# Dilbert-Badge.net
KiCad netlist of a schematic drawn in EAGLE
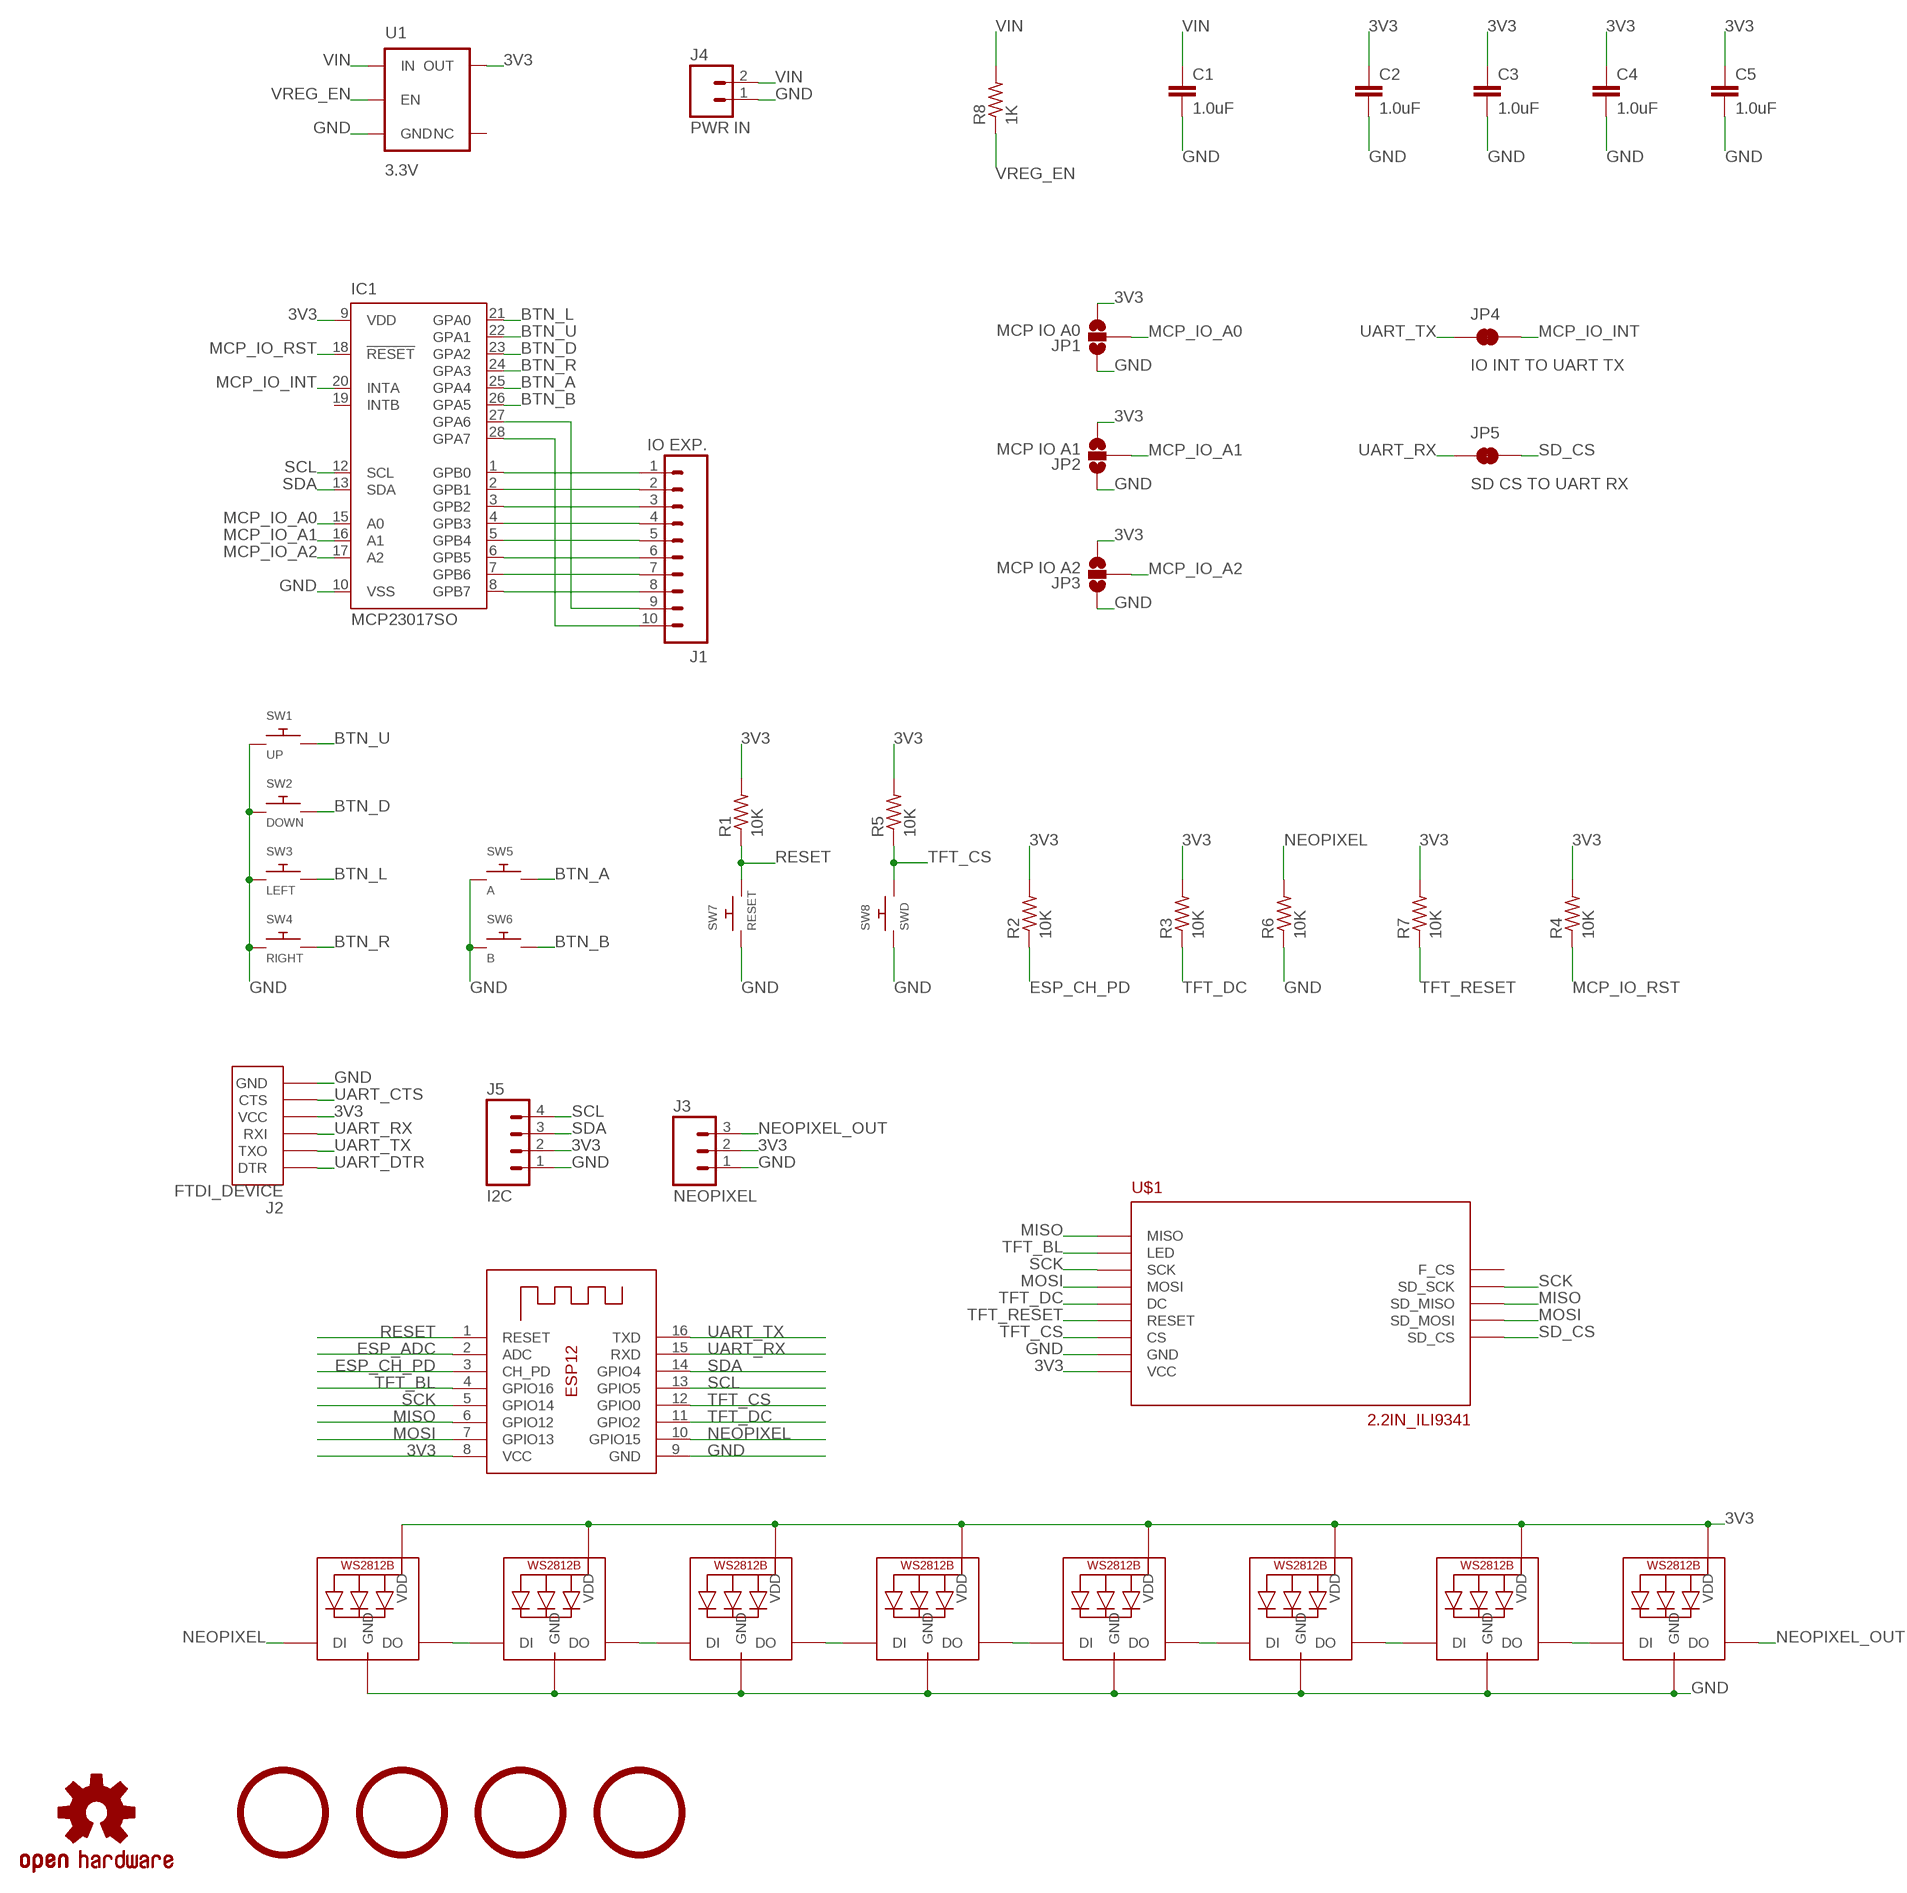
[diagram p0: schematic, sheet 1]

(export (version "E")
  (design (tool "Eeschema 10.0.6"))
  (components
    (comp (ref "C1")
      (value "1.0uF")
      (footprint "eagle-import:0805-CAP")
      (libsource (lib "eagle-import") (part "1.0UF-25V-+80/-20(0805){dblquote}"))
    )
    (comp (ref "C2")
      (value "1.0uF")
      (footprint "eagle-import:0805-CAP")
      (libsource (lib "eagle-import") (part "1.0UF-25V-+80/-20(0805){dblquote}"))
    )
    (comp (ref "C3")
      (value "1.0uF")
      (footprint "eagle-import:0805-CAP")
      (libsource (lib "eagle-import") (part "1.0UF-25V-+80/-20(0805){dblquote}"))
    )
    (comp (ref "C4")
      (value "1.0uF")
      (footprint "eagle-import:0805-CAP")
      (libsource (lib "eagle-import") (part "1.0UF-25V-+80/-20(0805){dblquote}"))
    )
    (comp (ref "C5")
      (value "1.0uF")
      (footprint "eagle-import:0805-CAP")
      (libsource (lib "eagle-import") (part "1.0UF-25V-+80/-20(0805){dblquote}"))
    )
    (comp (ref "IC1")
      (value "MCP23017SO")
      (footprint "eagle-import:SO28W")
      (libsource (lib "eagle-import") (part "MCP23017SO"))
    )
    (comp (ref "J1")
      (value "IO EXP.")
      (footprint "eagle-import:1X10")
      (libsource (lib "eagle-import") (part "M10SILK_FEMALE_PTH"))
    )
    (comp (ref "J2")
      (value "FTDI_DEVICE")
      (footprint "eagle-import:FTDI_DEVICE_SIDE")
      (libsource (lib "eagle-import") (part "FTDI_DEVICE"))
    )
    (comp (ref "J3")
      (value "NEOPIXEL")
      (footprint "eagle-import:1X03")
      (libsource (lib "eagle-import") (part "M03PTH"))
    )
    (comp (ref "J4")
      (value "PWR IN")
      (footprint "eagle-import:1X02")
      (libsource (lib "eagle-import") (part "M02PTH"))
    )
    (comp (ref "J5")
      (value "I2C")
      (footprint "eagle-import:1X04")
      (libsource (lib "eagle-import") (part "M04PTH"))
    )
    (comp (ref "JP1")
      (value "MCP IO A0")
      (footprint "eagle-import:PAD-JUMPER-3-NO_YES_SILK")
      (libsource (lib "eagle-import") (part "JUMPER-PAD-3-NOYES_SILK"))
    )
    (comp (ref "JP2")
      (value "MCP IO A1")
      (footprint "eagle-import:PAD-JUMPER-3-NO_YES_SILK")
      (libsource (lib "eagle-import") (part "JUMPER-PAD-3-NOYES_SILK"))
    )
    (comp (ref "JP3")
      (value "MCP IO A2")
      (footprint "eagle-import:PAD-JUMPER-3-NO_YES_SILK")
      (libsource (lib "eagle-import") (part "JUMPER-PAD-3-NOYES_SILK"))
    )
    (comp (ref "JP4")
      (value "IO INT TO UART TX")
      (footprint "eagle-import:PAD-JUMPER-2-NC_BY_TRACE_NO_SILK")
      (libsource (lib "eagle-import") (part "JUMPER-PAD-2-NC_BY_TRACENO_SILK"))
    )
    (comp (ref "JP5")
      (value "SD CS TO UART RX")
      (footprint "eagle-import:PAD-JUMPER-2-NC_BY_TRACE_NO_SILK")
      (libsource (lib "eagle-import") (part "JUMPER-PAD-2-NC_BY_TRACENO_SILK"))
    )
    (comp (ref "LED1")
      (value "WS2812B5050")
      (footprint "eagle-import:WS2812B")
      (libsource (lib "eagle-import") (part "WS2812B5050"))
    )
    (comp (ref "LED2")
      (value "WS2812B5050")
      (footprint "eagle-import:WS2812B")
      (libsource (lib "eagle-import") (part "WS2812B5050"))
    )
    (comp (ref "LED3")
      (value "WS2812B5050")
      (footprint "eagle-import:WS2812B")
      (libsource (lib "eagle-import") (part "WS2812B5050"))
    )
    (comp (ref "LED4")
      (value "WS2812B5050")
      (footprint "eagle-import:WS2812B")
      (libsource (lib "eagle-import") (part "WS2812B5050"))
    )
    (comp (ref "LED5")
      (value "WS2812B5050")
      (footprint "eagle-import:WS2812B")
      (libsource (lib "eagle-import") (part "WS2812B5050"))
    )
    (comp (ref "LED6")
      (value "WS2812B5050")
      (footprint "eagle-import:WS2812B")
      (libsource (lib "eagle-import") (part "WS2812B5050"))
    )
    (comp (ref "LED7")
      (value "WS2812B5050")
      (footprint "eagle-import:WS2812B")
      (libsource (lib "eagle-import") (part "WS2812B5050"))
    )
    (comp (ref "LED8")
      (value "WS2812B5050")
      (footprint "eagle-import:WS2812B")
      (libsource (lib "eagle-import") (part "WS2812B5050"))
    )
    (comp (ref "LOGO1")
      (value "OSHW-LOGOL")
      (footprint "eagle-import:OSHW-LOGO-L")
      (libsource (lib "eagle-import") (part "OSHW-LOGOL"))
    )
    (comp (ref "R1")
      (value "10K")
      (footprint "eagle-import:R0805")
      (libsource (lib "eagle-import") (part "R-US_R0805"))
    )
    (comp (ref "R2")
      (value "10K")
      (footprint "eagle-import:R0805")
      (libsource (lib "eagle-import") (part "R-US_R0805"))
    )
    (comp (ref "R3")
      (value "10K")
      (footprint "eagle-import:R0805")
      (libsource (lib "eagle-import") (part "R-US_R0805"))
    )
    (comp (ref "R4")
      (value "10K")
      (footprint "eagle-import:R0805")
      (libsource (lib "eagle-import") (part "R-US_R0805"))
    )
    (comp (ref "R5")
      (value "10K")
      (footprint "eagle-import:R0805")
      (libsource (lib "eagle-import") (part "R-US_R0805"))
    )
    (comp (ref "R6")
      (value "10K")
      (footprint "eagle-import:R0805")
      (libsource (lib "eagle-import") (part "R-US_R0805"))
    )
    (comp (ref "R7")
      (value "10K")
      (footprint "eagle-import:R0805")
      (libsource (lib "eagle-import") (part "R-US_R0805"))
    )
    (comp (ref "R8")
      (value "1K")
      (footprint "eagle-import:R0805")
      (libsource (lib "eagle-import") (part "R-US_R0805"))
    )
    (comp (ref "SW1")
      (value "UP")
      (footprint "eagle-import:TACT_PANA-EVQ")
      (libsource (lib "eagle-import") (part "SWITCH_PUSHBUTTONEVQ-PE"))
    )
    (comp (ref "SW2")
      (value "DOWN")
      (footprint "eagle-import:TACT_PANA-EVQ")
      (libsource (lib "eagle-import") (part "SWITCH_PUSHBUTTONEVQ-PE"))
    )
    (comp (ref "SW3")
      (value "LEFT")
      (footprint "eagle-import:TACT_PANA-EVQ")
      (libsource (lib "eagle-import") (part "SWITCH_PUSHBUTTONEVQ-PE"))
    )
    (comp (ref "SW4")
      (value "RIGHT")
      (footprint "eagle-import:TACT_PANA-EVQ")
      (libsource (lib "eagle-import") (part "SWITCH_PUSHBUTTONEVQ-PE"))
    )
    (comp (ref "SW5")
      (value "A")
      (footprint "eagle-import:TACT_PANA-EVQ")
      (libsource (lib "eagle-import") (part "SWITCH_PUSHBUTTONEVQ-PE"))
    )
    (comp (ref "SW6")
      (value "B")
      (footprint "eagle-import:TACT_PANA-EVQ")
      (libsource (lib "eagle-import") (part "SWITCH_PUSHBUTTONEVQ-PE"))
    )
    (comp (ref "SW7")
      (value "RESET")
      (footprint "eagle-import:TACT_PANA-EVQ")
      (libsource (lib "eagle-import") (part "SWITCH_PUSHBUTTONEVQ-PE"))
    )
    (comp (ref "SW8")
      (value "SWD")
      (footprint "eagle-import:TACT_PANA-EVQ")
      (libsource (lib "eagle-import") (part "SWITCH_PUSHBUTTONEVQ-PE"))
    )
    (comp (ref "U$1")
      (value "2.2IN_ILI9341")
      (footprint "eagle-import:2.2IN_ILI9341")
      (libsource (lib "eagle-import") (part "2.2IN_ILI9341"))
    )
    (comp (ref "U$2")
      (value "5MM_MOUNTING_HOLE")
      (footprint "eagle-import:5MM_HOLE")
      (libsource (lib "eagle-import") (part "5MM_MOUNTING_HOLE"))
    )
    (comp (ref "U$3")
      (value "5MM_MOUNTING_HOLE")
      (footprint "eagle-import:5MM_HOLE")
      (libsource (lib "eagle-import") (part "5MM_MOUNTING_HOLE"))
    )
    (comp (ref "U$4")
      (value "5MM_MOUNTING_HOLE")
      (footprint "eagle-import:5MM_HOLE")
      (libsource (lib "eagle-import") (part "5MM_MOUNTING_HOLE"))
    )
    (comp (ref "U$5")
      (value "5MM_MOUNTING_HOLE")
      (footprint "eagle-import:5MM_HOLE")
      (libsource (lib "eagle-import") (part "5MM_MOUNTING_HOLE"))
    )
    (comp (ref "U1")
      (value "3.3V")
      (footprint "eagle-import:SOT23-5")
      (libsource (lib "eagle-import") (part "V_REG_AP2112K-3.3V"))
    )
    (comp (ref "X1")
      (value "ESP-12")
      (footprint "eagle-import:ESP-12")
      (libsource (lib "eagle-import") (part "ESP-12"))
    )
  )
  (nets
    (net (code "1") (name "/3V3") (class "Default")
      (node (ref "C2") (pin "1") (pinfunction "1_1") (pintype "passive"))
      (node (ref "C3") (pin "1") (pinfunction "1_1") (pintype "passive"))
      (node (ref "C4") (pin "1") (pinfunction "1_1") (pintype "passive"))
      (node (ref "C5") (pin "1") (pinfunction "1_1") (pintype "passive"))
      (node (ref "IC1") (pin "9") (pinfunction "VDD_9") (pintype "power_in"))
      (node (ref "J2") (pin "P$4") (pinfunction "VCC_P$4") (pintype "bidirectional"))
      (node (ref "J3") (pin "2") (pinfunction "2_2") (pintype "passive"))
      (node (ref "J5") (pin "2") (pinfunction "2_2") (pintype "passive"))
      (node (ref "JP1") (pin "3") (pinfunction "3_3") (pintype "passive"))
      (node (ref "JP2") (pin "3") (pinfunction "3_3") (pintype "passive"))
      (node (ref "JP3") (pin "3") (pinfunction "3_3") (pintype "passive"))
      (node (ref "LED1") (pin "1-VDD") (pinfunction "VDD_1-VDD") (pintype "power_in"))
      (node (ref "LED2") (pin "1-VDD") (pinfunction "VDD_1-VDD") (pintype "power_in"))
      (node (ref "LED3") (pin "1-VDD") (pinfunction "VDD_1-VDD") (pintype "power_in"))
      (node (ref "LED4") (pin "1-VDD") (pinfunction "VDD_1-VDD") (pintype "power_in"))
      (node (ref "LED5") (pin "1-VDD") (pinfunction "VDD_1-VDD") (pintype "power_in"))
      (node (ref "LED6") (pin "1-VDD") (pinfunction "VDD_1-VDD") (pintype "power_in"))
      (node (ref "LED7") (pin "1-VDD") (pinfunction "VDD_1-VDD") (pintype "power_in"))
      (node (ref "LED8") (pin "1-VDD") (pinfunction "VDD_1-VDD") (pintype "power_in"))
      (node (ref "R1") (pin "2") (pinfunction "2_2") (pintype "passive"))
      (node (ref "R2") (pin "2") (pinfunction "2_2") (pintype "passive"))
      (node (ref "R3") (pin "2") (pinfunction "2_2") (pintype "passive"))
      (node (ref "R4") (pin "2") (pinfunction "2_2") (pintype "passive"))
      (node (ref "R5") (pin "2") (pinfunction "2_2") (pintype "passive"))
      (node (ref "R7") (pin "2") (pinfunction "2_2") (pintype "passive"))
      (node (ref "U$1") (pin "VCC") (pinfunction "VCC_VCC") (pintype "power_in"))
      (node (ref "U1") (pin "5") (pinfunction "OUT_5") (pintype "passive"))
      (node (ref "X1") (pin "8") (pinfunction "VCC_8") (pintype "power_in"))
    )
    (net (code "2") (name "/BTN_A") (class "Default")
      (node (ref "IC1") (pin "25") (pinfunction "GPA4_25") (pintype "bidirectional"))
      (node (ref "SW5") (pin "P$2") (pinfunction "P$2_P$2") (pintype "passive"))
    )
    (net (code "3") (name "/BTN_B") (class "Default")
      (node (ref "IC1") (pin "26") (pinfunction "GPA5_26") (pintype "bidirectional"))
      (node (ref "SW6") (pin "P$2") (pinfunction "P$2_P$2") (pintype "passive"))
    )
    (net (code "4") (name "/BTN_D") (class "Default")
      (node (ref "IC1") (pin "23") (pinfunction "GPA2_23") (pintype "bidirectional"))
      (node (ref "SW2") (pin "P$2") (pinfunction "P$2_P$2") (pintype "passive"))
    )
    (net (code "5") (name "/BTN_L") (class "Default")
      (node (ref "IC1") (pin "21") (pinfunction "GPA0_21") (pintype "bidirectional"))
      (node (ref "SW3") (pin "P$2") (pinfunction "P$2_P$2") (pintype "passive"))
    )
    (net (code "6") (name "/BTN_R") (class "Default")
      (node (ref "IC1") (pin "24") (pinfunction "GPA3_24") (pintype "bidirectional"))
      (node (ref "SW4") (pin "P$2") (pinfunction "P$2_P$2") (pintype "passive"))
    )
    (net (code "7") (name "/BTN_U") (class "Default")
      (node (ref "IC1") (pin "22") (pinfunction "GPA1_22") (pintype "bidirectional"))
      (node (ref "SW1") (pin "P$2") (pinfunction "P$2_P$2") (pintype "passive"))
    )
    (net (code "8") (name "/ESP_ADC") (class "Default")
      (node (ref "X1") (pin "2") (pinfunction "ADC_2") (pintype "passive"))
    )
    (net (code "9") (name "/ESP_CH_PD") (class "Default")
      (node (ref "R2") (pin "1") (pinfunction "1_1") (pintype "passive"))
      (node (ref "X1") (pin "3") (pinfunction "CH_PD_3") (pintype "input"))
    )
    (net (code "10") (name "/GND") (class "Default")
      (node (ref "C1") (pin "2") (pinfunction "2_2") (pintype "passive"))
      (node (ref "C2") (pin "2") (pinfunction "2_2") (pintype "passive"))
      (node (ref "C3") (pin "2") (pinfunction "2_2") (pintype "passive"))
      (node (ref "C4") (pin "2") (pinfunction "2_2") (pintype "passive"))
      (node (ref "C5") (pin "2") (pinfunction "2_2") (pintype "passive"))
      (node (ref "IC1") (pin "10") (pinfunction "VSS_10") (pintype "power_in"))
      (node (ref "J2") (pin "P$6") (pinfunction "GND_P$6") (pintype "bidirectional"))
      (node (ref "J3") (pin "1") (pinfunction "1_1") (pintype "passive"))
      (node (ref "J4") (pin "1") (pinfunction "1_1") (pintype "passive"))
      (node (ref "J5") (pin "1") (pinfunction "1_1") (pintype "passive"))
      (node (ref "JP1") (pin "1") (pinfunction "1_1") (pintype "passive"))
      (node (ref "JP2") (pin "1") (pinfunction "1_1") (pintype "passive"))
      (node (ref "JP3") (pin "1") (pinfunction "1_1") (pintype "passive"))
      (node (ref "LED1") (pin "3-GND") (pinfunction "GND_3-GND") (pintype "power_in"))
      (node (ref "LED2") (pin "3-GND") (pinfunction "GND_3-GND") (pintype "power_in"))
      (node (ref "LED3") (pin "3-GND") (pinfunction "GND_3-GND") (pintype "power_in"))
      (node (ref "LED4") (pin "3-GND") (pinfunction "GND_3-GND") (pintype "power_in"))
      (node (ref "LED5") (pin "3-GND") (pinfunction "GND_3-GND") (pintype "power_in"))
      (node (ref "LED6") (pin "3-GND") (pinfunction "GND_3-GND") (pintype "power_in"))
      (node (ref "LED7") (pin "3-GND") (pinfunction "GND_3-GND") (pintype "power_in"))
      (node (ref "LED8") (pin "3-GND") (pinfunction "GND_3-GND") (pintype "power_in"))
      (node (ref "R6") (pin "1") (pinfunction "1_1") (pintype "passive"))
      (node (ref "SW1") (pin "P$1") (pinfunction "P$1_P$1") (pintype "passive"))
      (node (ref "SW2") (pin "P$1") (pinfunction "P$1_P$1") (pintype "passive"))
      (node (ref "SW3") (pin "P$1") (pinfunction "P$1_P$1") (pintype "passive"))
      (node (ref "SW4") (pin "P$1") (pinfunction "P$1_P$1") (pintype "passive"))
      (node (ref "SW5") (pin "P$1") (pinfunction "P$1_P$1") (pintype "passive"))
      (node (ref "SW6") (pin "P$1") (pinfunction "P$1_P$1") (pintype "passive"))
      (node (ref "SW7") (pin "P$1") (pinfunction "P$1_P$1") (pintype "passive"))
      (node (ref "SW8") (pin "P$1") (pinfunction "P$1_P$1") (pintype "passive"))
      (node (ref "U$1") (pin "GND") (pinfunction "GND_GND") (pintype "power_in"))
      (node (ref "U1") (pin "2") (pinfunction "GND_2") (pintype "input"))
      (node (ref "X1") (pin "9") (pinfunction "GND_9") (pintype "power_in"))
    )
    (net (code "11") (name "/MCP_IO_A0") (class "Default")
      (node (ref "IC1") (pin "15") (pinfunction "A0_15") (pintype "input"))
      (node (ref "JP1") (pin "2") (pinfunction "2_2") (pintype "passive"))
    )
    (net (code "12") (name "/MCP_IO_A1") (class "Default")
      (node (ref "IC1") (pin "16") (pinfunction "A1_16") (pintype "input"))
      (node (ref "JP2") (pin "2") (pinfunction "2_2") (pintype "passive"))
    )
    (net (code "13") (name "/MCP_IO_A2") (class "Default")
      (node (ref "IC1") (pin "17") (pinfunction "A2_17") (pintype "input"))
      (node (ref "JP3") (pin "2") (pinfunction "2_2") (pintype "passive"))
    )
    (net (code "14") (name "/MCP_IO_INT") (class "Default")
      (node (ref "IC1") (pin "20") (pinfunction "INTA_20") (pintype "output"))
      (node (ref "JP4") (pin "2") (pinfunction "2_2") (pintype "passive"))
    )
    (net (code "15") (name "/MCP_IO_RST") (class "Default")
      (node (ref "IC1") (pin "18") (pinfunction "~{RESET}_18") (pintype "input"))
      (node (ref "R4") (pin "1") (pinfunction "1_1") (pintype "passive"))
    )
    (net (code "16") (name "/MISO") (class "Default")
      (node (ref "U$1") (pin "MISO") (pinfunction "MISO_MISO") (pintype "output"))
      (node (ref "U$1") (pin "SD_MISO") (pinfunction "SD_MISO_SD_MISO") (pintype "output"))
      (node (ref "X1") (pin "6") (pinfunction "GPIO12_6") (pintype "bidirectional"))
    )
    (net (code "17") (name "/MOSI") (class "Default")
      (node (ref "U$1") (pin "MOSI") (pinfunction "MOSI_MOSI") (pintype "input"))
      (node (ref "U$1") (pin "SD_MOSI") (pinfunction "SD_MOSI_SD_MOSI") (pintype "input"))
      (node (ref "X1") (pin "7") (pinfunction "GPIO13_7") (pintype "bidirectional"))
    )
    (net (code "18") (name "/NEOPIXEL") (class "Default")
      (node (ref "LED1") (pin "4-DIN") (pinfunction "DI_4-DIN") (pintype "input"))
      (node (ref "R6") (pin "2") (pinfunction "2_2") (pintype "passive"))
      (node (ref "X1") (pin "10") (pinfunction "GPIO15_10") (pintype "bidirectional"))
    )
    (net (code "19") (name "/NEOPIXEL_OUT") (class "Default")
      (node (ref "J3") (pin "3") (pinfunction "3_3") (pintype "passive"))
      (node (ref "LED8") (pin "2-DOUT") (pinfunction "DO_2-DOUT") (pintype "output"))
    )
    (net (code "20") (name "/RESET") (class "Default")
      (node (ref "R1") (pin "1") (pinfunction "1_1") (pintype "passive"))
      (node (ref "SW7") (pin "P$2") (pinfunction "P$2_P$2") (pintype "passive"))
      (node (ref "X1") (pin "1") (pinfunction "RESET_1") (pintype "input"))
    )
    (net (code "21") (name "/SCK") (class "Default")
      (node (ref "U$1") (pin "SCK") (pinfunction "SCK_SCK") (pintype "input"))
      (node (ref "U$1") (pin "SD_SCK") (pinfunction "SD_SCK_SD_SCK") (pintype "input"))
      (node (ref "X1") (pin "5") (pinfunction "GPIO14_5") (pintype "bidirectional"))
    )
    (net (code "22") (name "/SCL") (class "Default")
      (node (ref "IC1") (pin "12") (pinfunction "SCL_12") (pintype "input"))
      (node (ref "J5") (pin "4") (pinfunction "4_4") (pintype "passive"))
      (node (ref "X1") (pin "13") (pinfunction "GPIO5_13") (pintype "bidirectional"))
    )
    (net (code "23") (name "/SDA") (class "Default")
      (node (ref "IC1") (pin "13") (pinfunction "SDA_13") (pintype "bidirectional"))
      (node (ref "J5") (pin "3") (pinfunction "3_3") (pintype "passive"))
      (node (ref "X1") (pin "14") (pinfunction "GPIO4_14") (pintype "bidirectional"))
    )
    (net (code "24") (name "/SD_CS") (class "Default")
      (node (ref "JP5") (pin "2") (pinfunction "2_2") (pintype "passive"))
      (node (ref "U$1") (pin "SD_CS") (pinfunction "SD_CS_SD_CS") (pintype "input"))
    )
    (net (code "25") (name "/TFT_BL") (class "Default")
      (node (ref "U$1") (pin "LED") (pinfunction "LED_LED") (pintype "input"))
      (node (ref "X1") (pin "4") (pinfunction "GPIO16_4") (pintype "bidirectional"))
    )
    (net (code "26") (name "/TFT_CS") (class "Default")
      (node (ref "R5") (pin "1") (pinfunction "1_1") (pintype "passive"))
      (node (ref "SW8") (pin "P$2") (pinfunction "P$2_P$2") (pintype "passive"))
      (node (ref "U$1") (pin "CS") (pinfunction "CS_CS") (pintype "input"))
      (node (ref "X1") (pin "12") (pinfunction "GPIO0_12") (pintype "bidirectional"))
    )
    (net (code "27") (name "/TFT_DC") (class "Default")
      (node (ref "R3") (pin "1") (pinfunction "1_1") (pintype "passive"))
      (node (ref "U$1") (pin "DC") (pinfunction "DC_DC") (pintype "input"))
      (node (ref "X1") (pin "11") (pinfunction "GPIO2_11") (pintype "bidirectional"))
    )
    (net (code "28") (name "/TFT_RESET") (class "Default")
      (node (ref "R7") (pin "1") (pinfunction "1_1") (pintype "passive"))
      (node (ref "U$1") (pin "RESET") (pinfunction "RESET_RESET") (pintype "input"))
    )
    (net (code "29") (name "/UART_CTS") (class "Default")
      (node (ref "J2") (pin "P$5") (pinfunction "CTS_P$5") (pintype "bidirectional"))
    )
    (net (code "30") (name "/UART_DTR") (class "Default")
      (node (ref "J2") (pin "P$1") (pinfunction "DTR_P$1") (pintype "bidirectional"))
    )
    (net (code "31") (name "/UART_RX") (class "Default")
      (node (ref "J2") (pin "P$3") (pinfunction "RXI_P$3") (pintype "bidirectional"))
      (node (ref "JP5") (pin "1") (pinfunction "1_1") (pintype "passive"))
      (node (ref "X1") (pin "15") (pinfunction "RXD_15") (pintype "input"))
    )
    (net (code "32") (name "/UART_TX") (class "Default")
      (node (ref "J2") (pin "P$2") (pinfunction "TXO_P$2") (pintype "bidirectional"))
      (node (ref "JP4") (pin "1") (pinfunction "1_1") (pintype "passive"))
      (node (ref "X1") (pin "16") (pinfunction "TXD_16") (pintype "output"))
    )
    (net (code "33") (name "/VIN") (class "Default")
      (node (ref "C1") (pin "1") (pinfunction "1_1") (pintype "passive"))
      (node (ref "J4") (pin "2") (pinfunction "2_2") (pintype "passive"))
      (node (ref "R8") (pin "2") (pinfunction "2_2") (pintype "passive"))
      (node (ref "U1") (pin "1") (pinfunction "IN_1") (pintype "input"))
    )
    (net (code "34") (name "/VREG_EN") (class "Default")
      (node (ref "R8") (pin "1") (pinfunction "1_1") (pintype "passive"))
      (node (ref "U1") (pin "3") (pinfunction "EN_3") (pintype "input"))
    )
    (net (code "35") (name "Net-(IC1-GPA6)") (class "Default")
      (node (ref "IC1") (pin "27") (pinfunction "GPA6_27") (pintype "bidirectional"))
      (node (ref "J1") (pin "9") (pinfunction "9_9") (pintype "passive"))
    )
    (net (code "36") (name "Net-(IC1-GPA7)") (class "Default")
      (node (ref "IC1") (pin "28") (pinfunction "GPA7_28") (pintype "bidirectional"))
      (node (ref "J1") (pin "10") (pinfunction "10_10") (pintype "passive"))
    )
    (net (code "37") (name "Net-(IC1-GPB0)") (class "Default")
      (node (ref "IC1") (pin "1") (pinfunction "GPB0_1") (pintype "bidirectional"))
      (node (ref "J1") (pin "1") (pinfunction "1_1") (pintype "passive"))
    )
    (net (code "38") (name "Net-(IC1-GPB1)") (class "Default")
      (node (ref "IC1") (pin "2") (pinfunction "GPB1_2") (pintype "bidirectional"))
      (node (ref "J1") (pin "2") (pinfunction "2_2") (pintype "passive"))
    )
    (net (code "39") (name "Net-(IC1-GPB2)") (class "Default")
      (node (ref "IC1") (pin "3") (pinfunction "GPB2_3") (pintype "bidirectional"))
      (node (ref "J1") (pin "3") (pinfunction "3_3") (pintype "passive"))
    )
    (net (code "40") (name "Net-(IC1-GPB3)") (class "Default")
      (node (ref "IC1") (pin "4") (pinfunction "GPB3_4") (pintype "bidirectional"))
      (node (ref "J1") (pin "4") (pinfunction "4_4") (pintype "passive"))
    )
    (net (code "41") (name "Net-(IC1-GPB4)") (class "Default")
      (node (ref "IC1") (pin "5") (pinfunction "GPB4_5") (pintype "bidirectional"))
      (node (ref "J1") (pin "5") (pinfunction "5_5") (pintype "passive"))
    )
    (net (code "42") (name "Net-(IC1-GPB5)") (class "Default")
      (node (ref "IC1") (pin "6") (pinfunction "GPB5_6") (pintype "bidirectional"))
      (node (ref "J1") (pin "6") (pinfunction "6_6") (pintype "passive"))
    )
    (net (code "43") (name "Net-(IC1-GPB6)") (class "Default")
      (node (ref "IC1") (pin "7") (pinfunction "GPB6_7") (pintype "bidirectional"))
      (node (ref "J1") (pin "7") (pinfunction "7_7") (pintype "passive"))
    )
    (net (code "44") (name "Net-(IC1-GPB7)") (class "Default")
      (node (ref "IC1") (pin "8") (pinfunction "GPB7_8") (pintype "bidirectional"))
      (node (ref "J1") (pin "8") (pinfunction "8_8") (pintype "passive"))
    )
    (net (code "45") (name "Net-(LED1-DO)") (class "Default")
      (node (ref "LED1") (pin "2-DOUT") (pinfunction "DO_2-DOUT") (pintype "output"))
      (node (ref "LED2") (pin "4-DIN") (pinfunction "DI_4-DIN") (pintype "input"))
    )
    (net (code "46") (name "Net-(LED2-DO)") (class "Default")
      (node (ref "LED2") (pin "2-DOUT") (pinfunction "DO_2-DOUT") (pintype "output"))
      (node (ref "LED3") (pin "4-DIN") (pinfunction "DI_4-DIN") (pintype "input"))
    )
    (net (code "47") (name "Net-(LED3-DO)") (class "Default")
      (node (ref "LED3") (pin "2-DOUT") (pinfunction "DO_2-DOUT") (pintype "output"))
      (node (ref "LED4") (pin "4-DIN") (pinfunction "DI_4-DIN") (pintype "input"))
    )
    (net (code "48") (name "Net-(LED4-DO)") (class "Default")
      (node (ref "LED4") (pin "2-DOUT") (pinfunction "DO_2-DOUT") (pintype "output"))
      (node (ref "LED5") (pin "4-DIN") (pinfunction "DI_4-DIN") (pintype "input"))
    )
    (net (code "49") (name "Net-(LED5-DO)") (class "Default")
      (node (ref "LED5") (pin "2-DOUT") (pinfunction "DO_2-DOUT") (pintype "output"))
      (node (ref "LED6") (pin "4-DIN") (pinfunction "DI_4-DIN") (pintype "input"))
    )
    (net (code "50") (name "Net-(LED6-DO)") (class "Default")
      (node (ref "LED6") (pin "2-DOUT") (pinfunction "DO_2-DOUT") (pintype "output"))
      (node (ref "LED7") (pin "4-DIN") (pinfunction "DI_4-DIN") (pintype "input"))
    )
    (net (code "51") (name "Net-(LED7-DO)") (class "Default")
      (node (ref "LED7") (pin "2-DOUT") (pinfunction "DO_2-DOUT") (pintype "output"))
      (node (ref "LED8") (pin "4-DIN") (pinfunction "DI_4-DIN") (pintype "input"))
    )
    (net (code "52") (name "unconnected-(IC1-INTB-Pad19)") (class "Default")
      (node (ref "IC1") (pin "19") (pinfunction "INTB_19") (pintype "output"))
    )
    (net (code "53") (name "unconnected-(U$1-PadF_CS)") (class "Default")
      (node (ref "U$1") (pin "F_CS") (pinfunction "F_CS_F_CS") (pintype "bidirectional"))
    )
    (net (code "54") (name "unconnected-(U1-NC-Pad4)") (class "Default")
      (node (ref "U1") (pin "4") (pinfunction "NC_4") (pintype "input"))
    )
  )
)
